# Board-Power.net
KiCad netlist of a schematic drawn in Altium Designer
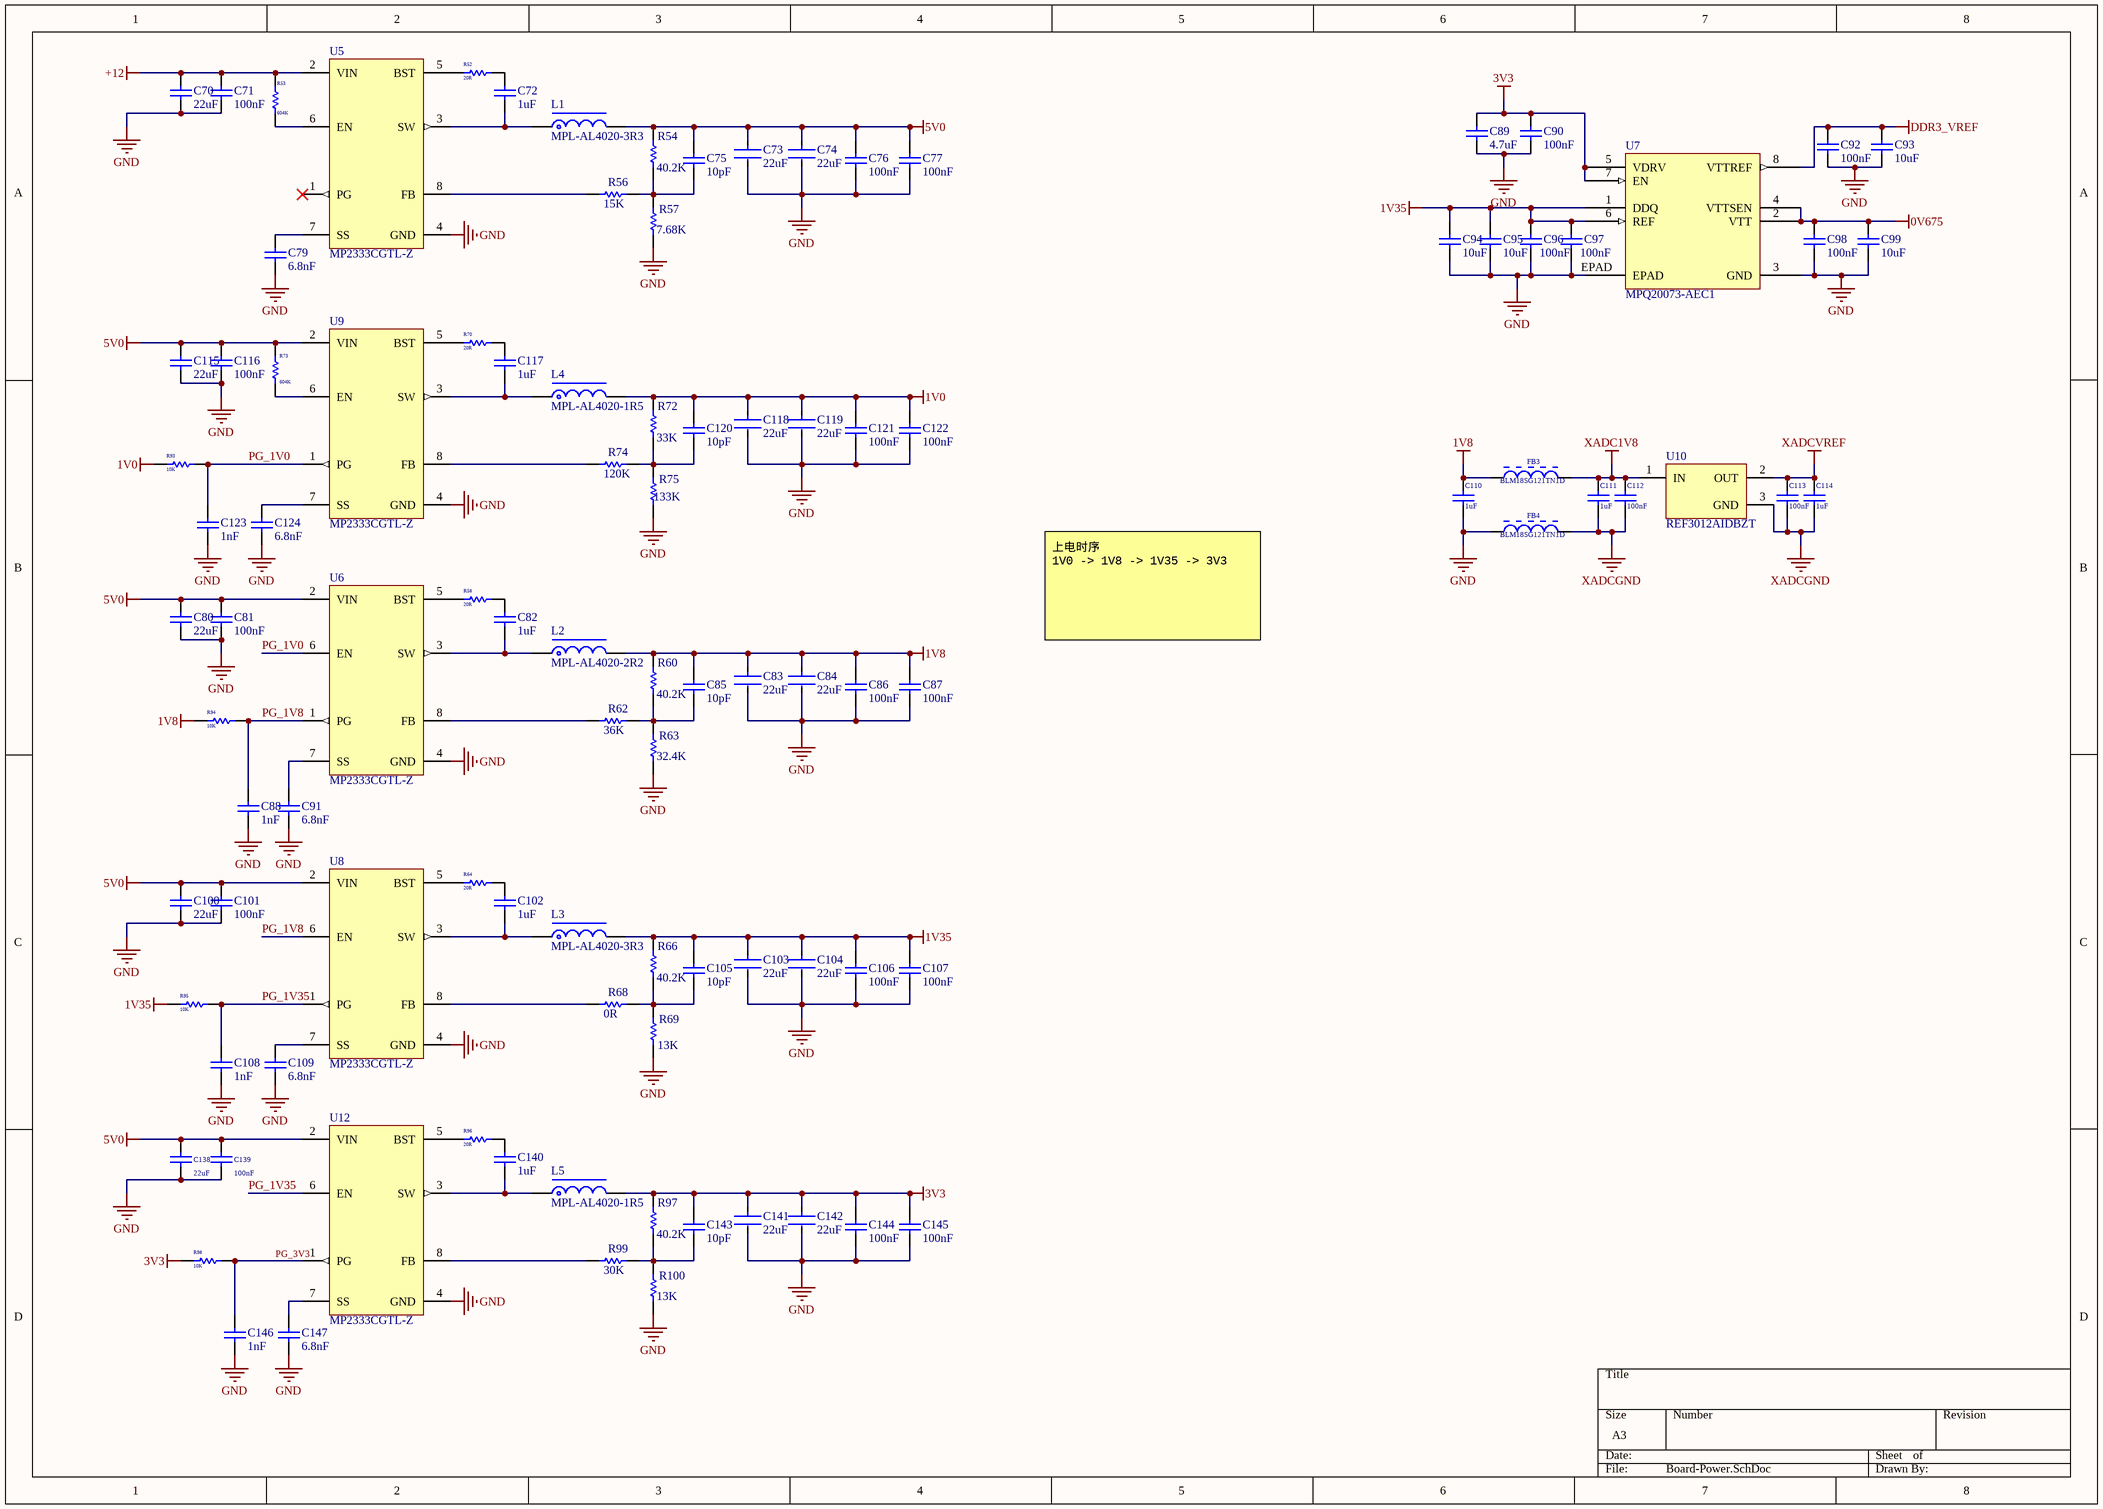
[diagram p0: Board-Power.SchDoc]

(export (version "E")
  (design (tool "Eeschema 10.0.6"))
  (components
    (comp (ref "C70")
      (value "22uF")
      (footprint "CAPC2013X145X45LL20T25")
      (description "GRM21BR61E226ME44L")
      (fields (field (name "MANUFACTURER") "Murata"))
      (libsource (lib "Altium Content Vault") (part "CAP"))
    )
    (comp (ref "C71")
      (value "100nF")
      (footprint "CAPC1005X55X25LL05T10")
      (fields (field (name "PART NUMBER") "GRM155R71H104KE14D") (field (name "MANUFACTURER") "Murata"))
      (libsource (lib "Altium Content Vault") (part "CAP"))
    )
    (comp (ref "C72")
      (value "1uF")
      (footprint "CAPC1005X55X25LL05T10")
      (fields (field (name "PART NUMBER") "GRM155R71H104KE14D") (field (name "MANUFACTURER") "Murata"))
      (libsource (lib "Altium Content Vault") (part "CAP"))
    )
    (comp (ref "C73")
      (value "22uF")
      (footprint "FP-GCM31C-0_2-e0_3_0_8-IPC_C")
      (description "GCM31CR71A226KE02K\r\nCap, Aec-Q200, 22Uf, 10V, Mlcc, 1206 Rohs Compliant: Yes")
      (libsource (lib "HainanU-RoboMaster-硬件组") (part "11868f565c42a9108669ba33697ecf6"))
    )
    (comp (ref "C74")
      (value "22uF")
      (footprint "FP-GCM31C-0_2-e0_3_0_8-IPC_C")
      (description "GCM31CR71A226KE02K\r\nCap, Aec-Q200, 22Uf, 10V, Mlcc, 1206 Rohs Compliant: Yes")
      (libsource (lib "HainanU-RoboMaster-硬件组") (part "11868f565c42a9108669ba33697ecf6"))
    )
    (comp (ref "C75")
      (value "10pF")
      (footprint "CAPC1005X55X25LL05T10")
      (fields (field (name "PART NUMBER") "GRM155R71H104KE14D") (field (name "MANUFACTURER") "Murata"))
      (libsource (lib "Altium Content Vault") (part "CAP"))
    )
    (comp (ref "C76")
      (value "100nF")
      (footprint "CAPC1005X55X25LL05T10")
      (fields (field (name "PART NUMBER") "GRM155R71H104KE14D") (field (name "MANUFACTURER") "Murata"))
      (libsource (lib "Altium Content Vault") (part "CAP"))
    )
    (comp (ref "C77")
      (value "100nF")
      (footprint "CAPC1005X55X25LL05T10")
      (fields (field (name "PART NUMBER") "GRM155R71H104KE14D") (field (name "MANUFACTURER") "Murata"))
      (libsource (lib "Altium Content Vault") (part "CAP"))
    )
    (comp (ref "C79")
      (value "6.8nF")
      (footprint "CAPC1005X55X25LL05T10")
      (fields (field (name "PART NUMBER") "GRM155R71H104KE14D") (field (name "MANUFACTURER") "Murata"))
      (libsource (lib "Altium Content Vault") (part "CAP"))
    )
    (comp (ref "C80")
      (value "22uF")
      (footprint "CAPC2013X145X45LL20T25")
      (description "GRM21BR61E226ME44L")
      (fields (field (name "MANUFACTURER") "Murata"))
      (libsource (lib "Altium Content Vault") (part "CAP"))
    )
    (comp (ref "C81")
      (value "100nF")
      (footprint "CAPC1005X55X25LL05T10")
      (fields (field (name "PART NUMBER") "GRM155R71H104KE14D") (field (name "MANUFACTURER") "Murata"))
      (libsource (lib "Altium Content Vault") (part "CAP"))
    )
    (comp (ref "C82")
      (value "1uF")
      (footprint "CAPC1005X55X25LL05T10")
      (fields (field (name "PART NUMBER") "GRM155R71H104KE14D") (field (name "MANUFACTURER") "Murata"))
      (libsource (lib "Altium Content Vault") (part "CAP"))
    )
    (comp (ref "C83")
      (value "22uF")
      (footprint "FP-GCM31C-0_2-e0_3_0_8-IPC_C")
      (description "GCM31CR71A226KE02K\r\nCap, Aec-Q200, 22Uf, 10V, Mlcc, 1206 Rohs Compliant: Yes")
      (libsource (lib "HainanU-RoboMaster-硬件组") (part "11868f565c42a9108669ba33697ecf6"))
    )
    (comp (ref "C84")
      (value "22uF")
      (footprint "FP-GCM31C-0_2-e0_3_0_8-IPC_C")
      (description "GCM31CR71A226KE02K\r\nCap, Aec-Q200, 22Uf, 10V, Mlcc, 1206 Rohs Compliant: Yes")
      (libsource (lib "HainanU-RoboMaster-硬件组") (part "11868f565c42a9108669ba33697ecf6"))
    )
    (comp (ref "C85")
      (value "10pF")
      (footprint "CAPC1005X55X25LL05T10")
      (fields (field (name "PART NUMBER") "GRM155R71H104KE14D") (field (name "MANUFACTURER") "Murata"))
      (libsource (lib "Altium Content Vault") (part "CAP"))
    )
    (comp (ref "C86")
      (value "100nF")
      (footprint "CAPC1005X55X25LL05T10")
      (fields (field (name "PART NUMBER") "GRM155R71H104KE14D") (field (name "MANUFACTURER") "Murata"))
      (libsource (lib "Altium Content Vault") (part "CAP"))
    )
    (comp (ref "C87")
      (value "100nF")
      (footprint "CAPC1005X55X25LL05T10")
      (fields (field (name "PART NUMBER") "GRM155R71H104KE14D") (field (name "MANUFACTURER") "Murata"))
      (libsource (lib "Altium Content Vault") (part "CAP"))
    )
    (comp (ref "C88")
      (value "1nF")
      (footprint "CAPC1005X55X25LL05T10")
      (fields (field (name "PART NUMBER") "GRM155R71H104KE14D") (field (name "MANUFACTURER") "Murata"))
      (libsource (lib "Altium Content Vault") (part "CAP"))
    )
    (comp (ref "C89")
      (value "4.7uF")
      (footprint "CAPC1005X55X25LL05T10")
      (fields (field (name "PART NUMBER") "GRM155R71H104KE14D") (field (name "MANUFACTURER") "Murata"))
      (libsource (lib "Altium Content Vault") (part "CAP"))
    )
    (comp (ref "C90")
      (value "100nF")
      (footprint "CAPC1005X55X25LL05T10")
      (fields (field (name "PART NUMBER") "GRM155R71H104KE14D") (field (name "MANUFACTURER") "Murata"))
      (libsource (lib "Altium Content Vault") (part "CAP"))
    )
    (comp (ref "C91")
      (value "6.8nF")
      (footprint "CAPC1005X55X25LL05T10")
      (fields (field (name "PART NUMBER") "GRM155R71H104KE14D") (field (name "MANUFACTURER") "Murata"))
      (libsource (lib "Altium Content Vault") (part "CAP"))
    )
    (comp (ref "C92")
      (value "100nF")
      (footprint "CAPC1005X55X25LL05T10")
      (fields (field (name "PART NUMBER") "GRM155R71H104KE14D") (field (name "MANUFACTURER") "Murata"))
      (libsource (lib "Altium Content Vault") (part "CAP"))
    )
    (comp (ref "C93")
      (value "10uF")
      (footprint "MURA-1206_H_1.8_L")
      (description "GRM31CR61H106KA12L\r\nCAP, Ceramic, 10 uF, 10%, 50 V, 1206, RoHS, Tape and Reel")
      (fields (field (name "TOLERANCE") "10%") (field (name "MANUFACTURER") "Murata"))
      (libsource (lib "Altium Content Vault") (part "CAP-NP-2"))
    )
    (comp (ref "C94")
      (value "10uF")
      (footprint "MURA-1206_H_1.8_L")
      (description "GRM31CR61H106KA12L\r\nCAP, Ceramic, 10 uF, 10%, 50 V, 1206, RoHS, Tape and Reel")
      (fields (field (name "TOLERANCE") "10%") (field (name "MANUFACTURER") "Murata"))
      (libsource (lib "Altium Content Vault") (part "CAP-NP-2"))
    )
    (comp (ref "C95")
      (value "10uF")
      (footprint "MURA-1206_H_1.8_L")
      (description "GRM31CR61H106KA12L\r\nCAP, Ceramic, 10 uF, 10%, 50 V, 1206, RoHS, Tape and Reel")
      (fields (field (name "TOLERANCE") "10%") (field (name "MANUFACTURER") "Murata"))
      (libsource (lib "Altium Content Vault") (part "CAP-NP-2"))
    )
    (comp (ref "C96")
      (value "100nF")
      (footprint "CAPC1005X55X25LL05T10")
      (fields (field (name "PART NUMBER") "GRM155R71H104KE14D") (field (name "MANUFACTURER") "Murata"))
      (libsource (lib "Altium Content Vault") (part "CAP"))
    )
    (comp (ref "C97")
      (value "100nF")
      (footprint "CAPC1005X55X25LL05T10")
      (fields (field (name "PART NUMBER") "GRM155R71H104KE14D") (field (name "MANUFACTURER") "Murata"))
      (libsource (lib "Altium Content Vault") (part "CAP"))
    )
    (comp (ref "C98")
      (value "100nF")
      (footprint "CAPC1005X55X25LL05T10")
      (fields (field (name "PART NUMBER") "GRM155R71H104KE14D") (field (name "MANUFACTURER") "Murata"))
      (libsource (lib "Altium Content Vault") (part "CAP"))
    )
    (comp (ref "C99")
      (value "10uF")
      (footprint "MURA-1206_H_1.8_L")
      (description "GRM31CR61H106KA12L\r\nCAP, Ceramic, 10 uF, 10%, 50 V, 1206, RoHS, Tape and Reel")
      (fields (field (name "TOLERANCE") "10%") (field (name "MANUFACTURER") "Murata"))
      (libsource (lib "Altium Content Vault") (part "CAP-NP-2"))
    )
    (comp (ref "C100")
      (value "22uF")
      (footprint "CAPC2013X145X45LL20T25")
      (description "GRM21BR61E226ME44L")
      (fields (field (name "MANUFACTURER") "Murata"))
      (libsource (lib "Altium Content Vault") (part "CAP"))
    )
    (comp (ref "C101")
      (value "100nF")
      (footprint "CAPC1005X55X25LL05T10")
      (fields (field (name "PART NUMBER") "GRM155R71H104KE14D") (field (name "MANUFACTURER") "Murata"))
      (libsource (lib "Altium Content Vault") (part "CAP"))
    )
    (comp (ref "C102")
      (value "1uF")
      (footprint "CAPC1005X55X25LL05T10")
      (fields (field (name "PART NUMBER") "GRM155R71H104KE14D") (field (name "MANUFACTURER") "Murata"))
      (libsource (lib "Altium Content Vault") (part "CAP"))
    )
    (comp (ref "C103")
      (value "22uF")
      (footprint "FP-GCM31C-0_2-e0_3_0_8-IPC_C")
      (description "GCM31CR71A226KE02K\r\nCap, Aec-Q200, 22Uf, 10V, Mlcc, 1206 Rohs Compliant: Yes")
      (libsource (lib "HainanU-RoboMaster-硬件组") (part "11868f565c42a9108669ba33697ecf6"))
    )
    (comp (ref "C104")
      (value "22uF")
      (footprint "FP-GCM31C-0_2-e0_3_0_8-IPC_C")
      (description "GCM31CR71A226KE02K\r\nCap, Aec-Q200, 22Uf, 10V, Mlcc, 1206 Rohs Compliant: Yes")
      (libsource (lib "HainanU-RoboMaster-硬件组") (part "11868f565c42a9108669ba33697ecf6"))
    )
    (comp (ref "C105")
      (value "10pF")
      (footprint "CAPC1005X55X25LL05T10")
      (fields (field (name "PART NUMBER") "GRM155R71H104KE14D") (field (name "MANUFACTURER") "Murata"))
      (libsource (lib "Altium Content Vault") (part "CAP"))
    )
    (comp (ref "C106")
      (value "100nF")
      (footprint "CAPC1005X55X25LL05T10")
      (fields (field (name "PART NUMBER") "GRM155R71H104KE14D") (field (name "MANUFACTURER") "Murata"))
      (libsource (lib "Altium Content Vault") (part "CAP"))
    )
    (comp (ref "C107")
      (value "100nF")
      (footprint "CAPC1005X55X25LL05T10")
      (fields (field (name "PART NUMBER") "GRM155R71H104KE14D") (field (name "MANUFACTURER") "Murata"))
      (libsource (lib "Altium Content Vault") (part "CAP"))
    )
    (comp (ref "C108")
      (value "1nF")
      (footprint "CAPC1005X55X25LL05T10")
      (fields (field (name "PART NUMBER") "GRM155R71H104KE14D") (field (name "MANUFACTURER") "Murata"))
      (libsource (lib "Altium Content Vault") (part "CAP"))
    )
    (comp (ref "C109")
      (value "6.8nF")
      (footprint "CAPC1005X55X25LL05T10")
      (fields (field (name "PART NUMBER") "GRM155R71H104KE14D") (field (name "MANUFACTURER") "Murata"))
      (libsource (lib "Altium Content Vault") (part "CAP"))
    )
    (comp (ref "C110")
      (value "1uF")
      (footprint "CAPC1005X55X25LL05T10")
      (fields (field (name "PART NUMBER") "GRM155R71H104KE14D") (field (name "MANUFACTURER") "Murata"))
      (libsource (lib "Altium Content Vault") (part "CAP"))
    )
    (comp (ref "C111")
      (value "1uF")
      (footprint "CAPC1005X55X25LL05T10")
      (fields (field (name "PART NUMBER") "GRM155R71H104KE14D") (field (name "MANUFACTURER") "Murata"))
      (libsource (lib "Altium Content Vault") (part "CAP"))
    )
    (comp (ref "C112")
      (value "100nF")
      (footprint "CAPC1005X55X25LL05T10")
      (fields (field (name "PART NUMBER") "GRM155R71H104KE14D") (field (name "MANUFACTURER") "Murata"))
      (libsource (lib "Altium Content Vault") (part "CAP"))
    )
    (comp (ref "C113")
      (value "100nF")
      (footprint "CAPC1005X55X25LL05T10")
      (fields (field (name "PART NUMBER") "GRM155R71H104KE14D") (field (name "MANUFACTURER") "Murata"))
      (libsource (lib "Altium Content Vault") (part "CAP"))
    )
    (comp (ref "C114")
      (value "1uF")
      (footprint "CAPC1005X55X25LL05T10")
      (fields (field (name "PART NUMBER") "GRM155R71H104KE14D") (field (name "MANUFACTURER") "Murata"))
      (libsource (lib "Altium Content Vault") (part "CAP"))
    )
    (comp (ref "C115")
      (value "22uF")
      (footprint "CAPC2013X145X45LL20T25")
      (description "GRM21BR61E226ME44L")
      (fields (field (name "MANUFACTURER") "Murata"))
      (libsource (lib "Altium Content Vault") (part "CAP"))
    )
    (comp (ref "C116")
      (value "100nF")
      (footprint "CAPC1005X55X25LL05T10")
      (fields (field (name "PART NUMBER") "GRM155R71H104KE14D") (field (name "MANUFACTURER") "Murata"))
      (libsource (lib "Altium Content Vault") (part "CAP"))
    )
    (comp (ref "C117")
      (value "1uF")
      (footprint "CAPC1005X55X25LL05T10")
      (fields (field (name "PART NUMBER") "GRM155R71H104KE14D") (field (name "MANUFACTURER") "Murata"))
      (libsource (lib "Altium Content Vault") (part "CAP"))
    )
    (comp (ref "C118")
      (value "22uF")
      (footprint "FP-GCM31C-0_2-e0_3_0_8-IPC_C")
      (description "GCM31CR71A226KE02K\r\nCap, Aec-Q200, 22Uf, 10V, Mlcc, 1206 Rohs Compliant: Yes")
      (libsource (lib "HainanU-RoboMaster-硬件组") (part "11868f565c42a9108669ba33697ecf6"))
    )
    (comp (ref "C119")
      (value "22uF")
      (footprint "FP-GCM31C-0_2-e0_3_0_8-IPC_C")
      (description "GCM31CR71A226KE02K\r\nCap, Aec-Q200, 22Uf, 10V, Mlcc, 1206 Rohs Compliant: Yes")
      (libsource (lib "HainanU-RoboMaster-硬件组") (part "11868f565c42a9108669ba33697ecf6"))
    )
    (comp (ref "C120")
      (value "10pF")
      (footprint "CAPC1005X55X25LL05T10")
      (fields (field (name "PART NUMBER") "GRM155R71H104KE14D") (field (name "MANUFACTURER") "Murata"))
      (libsource (lib "Altium Content Vault") (part "CAP"))
    )
    (comp (ref "C121")
      (value "100nF")
      (footprint "CAPC1005X55X25LL05T10")
      (fields (field (name "PART NUMBER") "GRM155R71H104KE14D") (field (name "MANUFACTURER") "Murata"))
      (libsource (lib "Altium Content Vault") (part "CAP"))
    )
    (comp (ref "C122")
      (value "100nF")
      (footprint "CAPC1005X55X25LL05T10")
      (fields (field (name "PART NUMBER") "GRM155R71H104KE14D") (field (name "MANUFACTURER") "Murata"))
      (libsource (lib "Altium Content Vault") (part "CAP"))
    )
    (comp (ref "C123")
      (value "1nF")
      (footprint "CAPC1005X55X25LL05T10")
      (fields (field (name "PART NUMBER") "GRM155R71H104KE14D") (field (name "MANUFACTURER") "Murata"))
      (libsource (lib "Altium Content Vault") (part "CAP"))
    )
    (comp (ref "C124")
      (value "6.8nF")
      (footprint "CAPC1005X55X25LL05T10")
      (fields (field (name "PART NUMBER") "GRM155R71H104KE14D") (field (name "MANUFACTURER") "Murata"))
      (libsource (lib "Altium Content Vault") (part "CAP"))
    )
    (comp (ref "C138")
      (value "22uF")
      (footprint "CAPC2013X145X45LL20T25")
      (description "GRM21BR61E226ME44L")
      (fields (field (name "MANUFACTURER") "Murata"))
      (libsource (lib "Altium Content Vault") (part "CAP"))
    )
    (comp (ref "C139")
      (value "100nF")
      (footprint "CAPC1005X55X25LL05T10")
      (fields (field (name "PART NUMBER") "GRM155R71H104KE14D") (field (name "MANUFACTURER") "Murata"))
      (libsource (lib "Altium Content Vault") (part "CAP"))
    )
    (comp (ref "C140")
      (value "1uF")
      (footprint "CAPC1005X55X25LL05T10")
      (fields (field (name "PART NUMBER") "GRM155R71H104KE14D") (field (name "MANUFACTURER") "Murata"))
      (libsource (lib "Altium Content Vault") (part "CAP"))
    )
    (comp (ref "C141")
      (value "22uF")
      (footprint "FP-GCM31C-0_2-e0_3_0_8-IPC_C")
      (description "GCM31CR71A226KE02K\r\nCap, Aec-Q200, 22Uf, 10V, Mlcc, 1206 Rohs Compliant: Yes")
      (libsource (lib "HainanU-RoboMaster-硬件组") (part "11868f565c42a9108669ba33697ecf6"))
    )
    (comp (ref "C142")
      (value "22uF")
      (footprint "FP-GCM31C-0_2-e0_3_0_8-IPC_C")
      (description "GCM31CR71A226KE02K\r\nCap, Aec-Q200, 22Uf, 10V, Mlcc, 1206 Rohs Compliant: Yes")
      (libsource (lib "HainanU-RoboMaster-硬件组") (part "11868f565c42a9108669ba33697ecf6"))
    )
    (comp (ref "C143")
      (value "10pF")
      (footprint "CAPC1005X55X25LL05T10")
      (fields (field (name "PART NUMBER") "GRM155R71H104KE14D") (field (name "MANUFACTURER") "Murata"))
      (libsource (lib "Altium Content Vault") (part "CAP"))
    )
    (comp (ref "C144")
      (value "100nF")
      (footprint "CAPC1005X55X25LL05T10")
      (fields (field (name "PART NUMBER") "GRM155R71H104KE14D") (field (name "MANUFACTURER") "Murata"))
      (libsource (lib "Altium Content Vault") (part "CAP"))
    )
    (comp (ref "C145")
      (value "100nF")
      (footprint "CAPC1005X55X25LL05T10")
      (fields (field (name "PART NUMBER") "GRM155R71H104KE14D") (field (name "MANUFACTURER") "Murata"))
      (libsource (lib "Altium Content Vault") (part "CAP"))
    )
    (comp (ref "C146")
      (value "1nF")
      (footprint "CAPC1005X55X25LL05T10")
      (fields (field (name "PART NUMBER") "GRM155R71H104KE14D") (field (name "MANUFACTURER") "Murata"))
      (libsource (lib "Altium Content Vault") (part "CAP"))
    )
    (comp (ref "C147")
      (value "6.8nF")
      (footprint "CAPC1005X55X25LL05T10")
      (fields (field (name "PART NUMBER") "GRM155R71H104KE14D") (field (name "MANUFACTURER") "Murata"))
      (libsource (lib "Altium Content Vault") (part "CAP"))
    )
    (comp (ref "FB3")
      (value "BLM18SG121TN1D")
      (footprint "MURA-BLM18SG-B40-CHIP-2_V6")
      (fields (field (name "MANUFACTURER") "Murata"))
      (libsource (lib "Altium Content Vault") (part "MURA-FB-2"))
    )
    (comp (ref "FB4")
      (value "BLM18SG121TN1D")
      (footprint "MURA-BLM18SG-B40-CHIP-2_V6")
      (fields (field (name "MANUFACTURER") "Murata"))
      (libsource (lib "Altium Content Vault") (part "MURA-FB-2"))
    )
    (comp (ref "L1")
      (value "MPL-AL4020-3R3")
      (footprint "MPL-AL4020")
      (description "一体成型电感")
      (libsource (lib "0.1 - 电阻-电容-电感-保险丝-晶振-晶体-磁珠-电位器-法拉电容-馈通电容") (part "L-Molding Choke"))
    )
    (comp (ref "L2")
      (value "MPL-AL4020-2R2")
      (footprint "MPL-AL4020")
      (description "一体成型电感")
      (libsource (lib "0.1 - 电阻-电容-电感-保险丝-晶振-晶体-磁珠-电位器-法拉电容-馈通电容") (part "L-Molding Choke"))
    )
    (comp (ref "L3")
      (value "MPL-AL4020-3R3")
      (footprint "MPL-AL4020")
      (description "一体成型电感")
      (libsource (lib "0.1 - 电阻-电容-电感-保险丝-晶振-晶体-磁珠-电位器-法拉电容-馈通电容") (part "L-Molding Choke"))
    )
    (comp (ref "L4")
      (value "MPL-AL4020-1R5")
      (footprint "MPL-AL4020")
      (description "一体成型电感")
      (libsource (lib "0.1 - 电阻-电容-电感-保险丝-晶振-晶体-磁珠-电位器-法拉电容-馈通电容") (part "L-Molding Choke"))
    )
    (comp (ref "L5")
      (value "MPL-AL4020-1R5")
      (footprint "MPL-AL4020")
      (description "一体成型电感")
      (libsource (lib "0.1 - 电阻-电容-电感-保险丝-晶振-晶体-磁珠-电位器-法拉电容-馈通电容") (part "L-Molding Choke"))
    )
    (comp (ref "R52")
      (value "20R")
      (footprint "RESC1005X40X25LL05T05")
      (fields (field (name "MANUFACTURER") "Panasonic") (field (name "PART NUMBER") "ERJ-2RKF40R2X"))
      (libsource (lib "Altium Content Vault") (part "RES"))
    )
    (comp (ref "R53")
      (value "604K")
      (footprint "RESC1005X40X25LL05T05")
      (fields (field (name "MANUFACTURER") "Panasonic") (field (name "PART NUMBER") "ERJ-2RKF40R2X"))
      (libsource (lib "Altium Content Vault") (part "RES"))
    )
    (comp (ref "R54")
      (value "40.2K")
      (footprint "RESC1005X40X25LL05T05")
      (fields (field (name "MANUFACTURER") "Panasonic") (field (name "PART NUMBER") "ERJ-2RKF40R2X"))
      (libsource (lib "Altium Content Vault") (part "RES"))
    )
    (comp (ref "R56")
      (value "15K")
      (footprint "RESC1005X40X25LL05T05")
      (fields (field (name "MANUFACTURER") "Panasonic") (field (name "PART NUMBER") "ERJ-2RKF40R2X"))
      (libsource (lib "Altium Content Vault") (part "RES"))
    )
    (comp (ref "R57")
      (value "7.68K")
      (footprint "RESC1005X40X25LL05T05")
      (fields (field (name "MANUFACTURER") "Panasonic") (field (name "PART NUMBER") "ERJ-2RKF40R2X"))
      (libsource (lib "Altium Content Vault") (part "RES"))
    )
    (comp (ref "R58")
      (value "20R")
      (footprint "RESC1005X40X25LL05T05")
      (fields (field (name "MANUFACTURER") "Panasonic") (field (name "PART NUMBER") "ERJ-2RKF40R2X"))
      (libsource (lib "Altium Content Vault") (part "RES"))
    )
    (comp (ref "R60")
      (value "40.2K")
      (footprint "RESC1005X40X25LL05T05")
      (fields (field (name "MANUFACTURER") "Panasonic") (field (name "PART NUMBER") "ERJ-2RKF40R2X"))
      (libsource (lib "Altium Content Vault") (part "RES"))
    )
    (comp (ref "R62")
      (value "36K")
      (footprint "RESC1005X40X25LL05T05")
      (fields (field (name "MANUFACTURER") "Panasonic") (field (name "PART NUMBER") "ERJ-2RKF40R2X"))
      (libsource (lib "Altium Content Vault") (part "RES"))
    )
    (comp (ref "R63")
      (value "32.4K")
      (footprint "RESC1005X40X25LL05T05")
      (fields (field (name "MANUFACTURER") "Panasonic") (field (name "PART NUMBER") "ERJ-2RKF40R2X"))
      (libsource (lib "Altium Content Vault") (part "RES"))
    )
    (comp (ref "R64")
      (value "20R")
      (footprint "RESC1005X40X25LL05T05")
      (fields (field (name "MANUFACTURER") "Panasonic") (field (name "PART NUMBER") "ERJ-2RKF40R2X"))
      (libsource (lib "Altium Content Vault") (part "RES"))
    )
    (comp (ref "R66")
      (value "40.2K")
      (footprint "RESC1005X40X25LL05T05")
      (fields (field (name "MANUFACTURER") "Panasonic") (field (name "PART NUMBER") "ERJ-2RKF40R2X"))
      (libsource (lib "Altium Content Vault") (part "RES"))
    )
    (comp (ref "R68")
      (value "0R")
      (footprint "RESC1005X40X25LL05T05")
      (fields (field (name "MANUFACTURER") "Panasonic") (field (name "PART NUMBER") "ERJ-2RKF40R2X"))
      (libsource (lib "Altium Content Vault") (part "RES"))
    )
    (comp (ref "R69")
      (value "13K")
      (footprint "RESC1005X40X25LL05T05")
      (fields (field (name "MANUFACTURER") "Panasonic") (field (name "PART NUMBER") "ERJ-2RKF40R2X"))
      (libsource (lib "Altium Content Vault") (part "RES"))
    )
    (comp (ref "R70")
      (value "20R")
      (footprint "RESC1005X40X25LL05T05")
      (fields (field (name "MANUFACTURER") "Panasonic") (field (name "PART NUMBER") "ERJ-2RKF40R2X"))
      (libsource (lib "Altium Content Vault") (part "RES"))
    )
    (comp (ref "R72")
      (value "33K")
      (footprint "RESC1005X40X25LL05T05")
      (fields (field (name "MANUFACTURER") "Panasonic") (field (name "PART NUMBER") "ERJ-2RKF40R2X"))
      (libsource (lib "Altium Content Vault") (part "RES"))
    )
    (comp (ref "R73")
      (value "604K")
      (footprint "RESC1005X40X25LL05T05")
      (fields (field (name "MANUFACTURER") "Panasonic") (field (name "PART NUMBER") "ERJ-2RKF40R2X"))
      (libsource (lib "Altium Content Vault") (part "RES"))
    )
    (comp (ref "R74")
      (value "120K")
      (footprint "RESC1005X40X25LL05T05")
      (fields (field (name "MANUFACTURER") "Panasonic") (field (name "PART NUMBER") "ERJ-2RKF40R2X"))
      (libsource (lib "Altium Content Vault") (part "RES"))
    )
    (comp (ref "R75")
      (value "133K")
      (footprint "RESC1005X40X25LL05T05")
      (fields (field (name "MANUFACTURER") "Panasonic") (field (name "PART NUMBER") "ERJ-2RKF40R2X"))
      (libsource (lib "Altium Content Vault") (part "RES"))
    )
    (comp (ref "R93")
      (value "10K")
      (footprint "RESC1005X40X25LL05T05")
      (fields (field (name "MANUFACTURER") "Panasonic") (field (name "PART NUMBER") "ERJ-2RKF40R2X"))
      (libsource (lib "Altium Content Vault") (part "RES"))
    )
    (comp (ref "R94")
      (value "10K")
      (footprint "RESC1005X40X25LL05T05")
      (fields (field (name "MANUFACTURER") "Panasonic") (field (name "PART NUMBER") "ERJ-2RKF40R2X"))
      (libsource (lib "Altium Content Vault") (part "RES"))
    )
    (comp (ref "R95")
      (value "10K")
      (footprint "RESC1005X40X25LL05T05")
      (fields (field (name "MANUFACTURER") "Panasonic") (field (name "PART NUMBER") "ERJ-2RKF40R2X"))
      (libsource (lib "Altium Content Vault") (part "RES"))
    )
    (comp (ref "R96")
      (value "20R")
      (footprint "RESC1005X40X25LL05T05")
      (fields (field (name "MANUFACTURER") "Panasonic") (field (name "PART NUMBER") "ERJ-2RKF40R2X"))
      (libsource (lib "Altium Content Vault") (part "RES"))
    )
    (comp (ref "R97")
      (value "40.2K")
      (footprint "RESC1005X40X25LL05T05")
      (fields (field (name "MANUFACTURER") "Panasonic") (field (name "PART NUMBER") "ERJ-2RKF40R2X"))
      (libsource (lib "Altium Content Vault") (part "RES"))
    )
    (comp (ref "R98")
      (value "10K")
      (footprint "RESC1005X40X25LL05T05")
      (fields (field (name "MANUFACTURER") "Panasonic") (field (name "PART NUMBER") "ERJ-2RKF40R2X"))
      (libsource (lib "Altium Content Vault") (part "RES"))
    )
    (comp (ref "R99")
      (value "30K")
      (footprint "RESC1005X40X25LL05T05")
      (fields (field (name "MANUFACTURER") "Panasonic") (field (name "PART NUMBER") "ERJ-2RKF40R2X"))
      (libsource (lib "Altium Content Vault") (part "RES"))
    )
    (comp (ref "R100")
      (value "13K")
      (footprint "RESC1005X40X25LL05T05")
      (fields (field (name "MANUFACTURER") "Panasonic") (field (name "PART NUMBER") "ERJ-2RKF40R2X"))
      (libsource (lib "Altium Content Vault") (part "RES"))
    )
    (comp (ref "U5")
      (value "MP2333CGTL-Z")
      (footprint "SOT583_MP2333C_MNP")
      (description "Switching Voltage Regulators 3A, 18V, 650kHz, Force CCM, Synchronous Step-Down C")
      (libsource (lib "HainanU-RoboMaster-硬件组") (part "MP2333CGTL-Z"))
    )
    (comp (ref "U6")
      (value "MP2333CGTL-Z")
      (footprint "SOT583_MP2333C_MNP")
      (description "Switching Voltage Regulators 3A, 18V, 650kHz, Force CCM, Synchronous Step-Down C")
      (libsource (lib "HainanU-RoboMaster-硬件组") (part "MP2333CGTL-Z"))
    )
    (comp (ref "U7")
      (value "MPQ20073-AEC1")
      (footprint "MSOP-8-EP_MNP-L")
      (description "2A 1.3V–6.0V DDR Memory Termination Regulator AEC-Q100 Qualified")
      (libsource (lib "HainanU-RoboMaster-硬件组") (part "MPQ20073DH-AEC1-LF-P"))
    )
    (comp (ref "U8")
      (value "MP2333CGTL-Z")
      (footprint "SOT583_MP2333C_MNP")
      (description "Switching Voltage Regulators 3A, 18V, 650kHz, Force CCM, Synchronous Step-Down C")
      (libsource (lib "HainanU-RoboMaster-硬件组") (part "MP2333CGTL-Z"))
    )
    (comp (ref "U9")
      (value "MP2333CGTL-Z")
      (footprint "SOT583_MP2333C_MNP")
      (description "Switching Voltage Regulators 3A, 18V, 650kHz, Force CCM, Synchronous Step-Down C")
      (libsource (lib "HainanU-RoboMaster-硬件组") (part "MP2333CGTL-Z"))
    )
    (comp (ref "U10")
      (value "REF3012AIDBZT")
      (footprint "DBZ0003A_L")
      (fields (field (name "MANUFACTURER") "Texas Instruments"))
      (libsource (lib "Altium Content Vault") (part "TI-REF3012DBZ3"))
    )
    (comp (ref "U12")
      (value "MP2333CGTL-Z")
      (footprint "SOT583_MP2333C_MNP")
      (description "Switching Voltage Regulators 3A, 18V, 650kHz, Force CCM, Synchronous Step-Down C")
      (libsource (lib "HainanU-RoboMaster-硬件组") (part "MP2333CGTL-Z"))
    )
  )
  (nets
    (net (code "1") (name "+12") (class "Default")
      (node (ref "C70") (pin "2") (pinfunction "2_2") (pintype "passive"))
      (node (ref "C71") (pin "2") (pinfunction "2_2") (pintype "passive"))
      (node (ref "R53") (pin "2") (pinfunction "2_2") (pintype "passive"))
      (node (ref "U5") (pin "2") (pinfunction "VIN_2") (pintype "power_in"))
    )
    (net (code "2") (name "/PG_1V0") (class "Default")
      (node (ref "C123") (pin "1") (pinfunction "1_1") (pintype "passive"))
      (node (ref "R93") (pin "1") (pinfunction "1_1") (pintype "passive"))
      (node (ref "U6") (pin "6") (pinfunction "EN_6") (pintype "passive"))
      (node (ref "U9") (pin "1") (pinfunction "PG_1") (pintype "output"))
    )
    (net (code "3") (name "/PG_1V8") (class "Default")
      (node (ref "C88") (pin "1") (pinfunction "1_1") (pintype "passive"))
      (node (ref "R94") (pin "1") (pinfunction "1_1") (pintype "passive"))
      (node (ref "U6") (pin "1") (pinfunction "PG_1") (pintype "output"))
      (node (ref "U8") (pin "6") (pinfunction "EN_6") (pintype "passive"))
    )
    (net (code "4") (name "/PG_1V35") (class "Default")
      (node (ref "C108") (pin "1") (pinfunction "1_1") (pintype "passive"))
      (node (ref "R95") (pin "1") (pinfunction "1_1") (pintype "passive"))
      (node (ref "U12") (pin "6") (pinfunction "EN_6") (pintype "passive"))
      (node (ref "U8") (pin "1") (pinfunction "PG_1") (pintype "output"))
    )
    (net (code "5") (name "/PG_3V3") (class "Default")
      (node (ref "C146") (pin "1") (pinfunction "1_1") (pintype "passive"))
      (node (ref "R98") (pin "1") (pinfunction "1_1") (pintype "passive"))
      (node (ref "U12") (pin "1") (pinfunction "PG_1") (pintype "output"))
    )
    (net (code "6") (name "0V675") (class "Default")
      (node (ref "C98") (pin "2") (pinfunction "2_2") (pintype "passive"))
      (node (ref "C99") (pin "2") (pinfunction "2_2") (pintype "passive"))
      (node (ref "U7") (pin "2") (pinfunction "VTT_2") (pintype "power_in"))
      (node (ref "U7") (pin "4") (pinfunction "VTTSEN_4") (pintype "passive"))
    )
    (net (code "7") (name "1V0") (class "Default")
      (node (ref "C118") (pin "1") (pinfunction "1_1") (pintype "passive"))
      (node (ref "C119") (pin "1") (pinfunction "1_1") (pintype "passive"))
      (node (ref "C120") (pin "2") (pinfunction "2_2") (pintype "passive"))
      (node (ref "C121") (pin "2") (pinfunction "2_2") (pintype "passive"))
      (node (ref "C122") (pin "2") (pinfunction "2_2") (pintype "passive"))
      (node (ref "L4") (pin "2") (pinfunction "2_2") (pintype "passive"))
      (node (ref "R72") (pin "1") (pinfunction "1_1") (pintype "passive"))
      (node (ref "R93") (pin "2") (pinfunction "2_2") (pintype "passive"))
    )
    (net (code "8") (name "1V8") (class "Default")
      (node (ref "C110") (pin "2") (pinfunction "2_2") (pintype "passive"))
      (node (ref "C83") (pin "1") (pinfunction "1_1") (pintype "passive"))
      (node (ref "C84") (pin "1") (pinfunction "1_1") (pintype "passive"))
      (node (ref "C85") (pin "2") (pinfunction "2_2") (pintype "passive"))
      (node (ref "C86") (pin "2") (pinfunction "2_2") (pintype "passive"))
      (node (ref "C87") (pin "2") (pinfunction "2_2") (pintype "passive"))
      (node (ref "FB3") (pin "1") (pinfunction "1_1") (pintype "passive"))
      (node (ref "L2") (pin "2") (pinfunction "2_2") (pintype "passive"))
      (node (ref "R60") (pin "1") (pinfunction "1_1") (pintype "passive"))
      (node (ref "R94") (pin "2") (pinfunction "2_2") (pintype "passive"))
    )
    (net (code "9") (name "1V35") (class "Default")
      (node (ref "C103") (pin "1") (pinfunction "1_1") (pintype "passive"))
      (node (ref "C104") (pin "1") (pinfunction "1_1") (pintype "passive"))
      (node (ref "C105") (pin "2") (pinfunction "2_2") (pintype "passive"))
      (node (ref "C106") (pin "2") (pinfunction "2_2") (pintype "passive"))
      (node (ref "C107") (pin "2") (pinfunction "2_2") (pintype "passive"))
      (node (ref "C94") (pin "2") (pinfunction "2_2") (pintype "passive"))
      (node (ref "C95") (pin "2") (pinfunction "2_2") (pintype "passive"))
      (node (ref "C96") (pin "2") (pinfunction "2_2") (pintype "passive"))
      (node (ref "C97") (pin "2") (pinfunction "2_2") (pintype "passive"))
      (node (ref "L3") (pin "2") (pinfunction "2_2") (pintype "passive"))
      (node (ref "R66") (pin "1") (pinfunction "1_1") (pintype "passive"))
      (node (ref "R95") (pin "2") (pinfunction "2_2") (pintype "passive"))
      (node (ref "U7") (pin "1") (pinfunction "DDQ_1") (pintype "power_in"))
      (node (ref "U7") (pin "6") (pinfunction "REF_6") (pintype "input"))
    )
    (net (code "10") (name "3V3") (class "Default")
      (node (ref "C141") (pin "1") (pinfunction "1_1") (pintype "passive"))
      (node (ref "C142") (pin "1") (pinfunction "1_1") (pintype "passive"))
      (node (ref "C143") (pin "2") (pinfunction "2_2") (pintype "passive"))
      (node (ref "C144") (pin "2") (pinfunction "2_2") (pintype "passive"))
      (node (ref "C145") (pin "2") (pinfunction "2_2") (pintype "passive"))
      (node (ref "C89") (pin "2") (pinfunction "2_2") (pintype "passive"))
      (node (ref "C90") (pin "2") (pinfunction "2_2") (pintype "passive"))
      (node (ref "L5") (pin "2") (pinfunction "2_2") (pintype "passive"))
      (node (ref "R97") (pin "1") (pinfunction "1_1") (pintype "passive"))
      (node (ref "R98") (pin "2") (pinfunction "2_2") (pintype "passive"))
      (node (ref "U7") (pin "5") (pinfunction "VDRV_5") (pintype "passive"))
      (node (ref "U7") (pin "7") (pinfunction "EN_7") (pintype "input"))
    )
    (net (code "11") (name "5V0") (class "Default")
      (node (ref "C100") (pin "2") (pinfunction "2_2") (pintype "passive"))
      (node (ref "C101") (pin "2") (pinfunction "2_2") (pintype "passive"))
      (node (ref "C115") (pin "2") (pinfunction "2_2") (pintype "passive"))
      (node (ref "C116") (pin "2") (pinfunction "2_2") (pintype "passive"))
      (node (ref "C138") (pin "2") (pinfunction "2_2") (pintype "passive"))
      (node (ref "C139") (pin "2") (pinfunction "2_2") (pintype "passive"))
      (node (ref "C73") (pin "1") (pinfunction "1_1") (pintype "passive"))
      (node (ref "C74") (pin "1") (pinfunction "1_1") (pintype "passive"))
      (node (ref "C75") (pin "2") (pinfunction "2_2") (pintype "passive"))
      (node (ref "C76") (pin "2") (pinfunction "2_2") (pintype "passive"))
      (node (ref "C77") (pin "2") (pinfunction "2_2") (pintype "passive"))
      (node (ref "C80") (pin "2") (pinfunction "2_2") (pintype "passive"))
      (node (ref "C81") (pin "2") (pinfunction "2_2") (pintype "passive"))
      (node (ref "L1") (pin "2") (pinfunction "2_2") (pintype "passive"))
      (node (ref "R54") (pin "1") (pinfunction "1_1") (pintype "passive"))
      (node (ref "R73") (pin "2") (pinfunction "2_2") (pintype "passive"))
      (node (ref "U12") (pin "2") (pinfunction "VIN_2") (pintype "power_in"))
      (node (ref "U6") (pin "2") (pinfunction "VIN_2") (pintype "power_in"))
      (node (ref "U8") (pin "2") (pinfunction "VIN_2") (pintype "power_in"))
      (node (ref "U9") (pin "2") (pinfunction "VIN_2") (pintype "power_in"))
    )
    (net (code "12") (name "DDR3_VREF") (class "Default")
      (node (ref "C92") (pin "2") (pinfunction "2_2") (pintype "passive"))
      (node (ref "C93") (pin "2") (pinfunction "2_2") (pintype "passive"))
      (node (ref "U7") (pin "8") (pinfunction "VTTREF_8") (pintype "output"))
    )
    (net (code "13") (name "GND") (class "Default")
      (node (ref "C100") (pin "1") (pinfunction "1_1") (pintype "passive"))
      (node (ref "C101") (pin "1") (pinfunction "1_1") (pintype "passive"))
      (node (ref "C103") (pin "2") (pinfunction "2_2") (pintype "passive"))
      (node (ref "C104") (pin "2") (pinfunction "2_2") (pintype "passive"))
      (node (ref "C106") (pin "1") (pinfunction "1_1") (pintype "passive"))
      (node (ref "C107") (pin "1") (pinfunction "1_1") (pintype "passive"))
      (node (ref "C108") (pin "2") (pinfunction "2_2") (pintype "passive"))
      (node (ref "C109") (pin "2") (pinfunction "2_2") (pintype "passive"))
      (node (ref "C110") (pin "1") (pinfunction "1_1") (pintype "passive"))
      (node (ref "C115") (pin "1") (pinfunction "1_1") (pintype "passive"))
      (node (ref "C116") (pin "1") (pinfunction "1_1") (pintype "passive"))
      (node (ref "C118") (pin "2") (pinfunction "2_2") (pintype "passive"))
      (node (ref "C119") (pin "2") (pinfunction "2_2") (pintype "passive"))
      (node (ref "C121") (pin "1") (pinfunction "1_1") (pintype "passive"))
      (node (ref "C122") (pin "1") (pinfunction "1_1") (pintype "passive"))
      (node (ref "C123") (pin "2") (pinfunction "2_2") (pintype "passive"))
      (node (ref "C124") (pin "2") (pinfunction "2_2") (pintype "passive"))
      (node (ref "C138") (pin "1") (pinfunction "1_1") (pintype "passive"))
      (node (ref "C139") (pin "1") (pinfunction "1_1") (pintype "passive"))
      (node (ref "C141") (pin "2") (pinfunction "2_2") (pintype "passive"))
      (node (ref "C142") (pin "2") (pinfunction "2_2") (pintype "passive"))
      (node (ref "C144") (pin "1") (pinfunction "1_1") (pintype "passive"))
      (node (ref "C145") (pin "1") (pinfunction "1_1") (pintype "passive"))
      (node (ref "C146") (pin "2") (pinfunction "2_2") (pintype "passive"))
      (node (ref "C147") (pin "2") (pinfunction "2_2") (pintype "passive"))
      (node (ref "C70") (pin "1") (pinfunction "1_1") (pintype "passive"))
      (node (ref "C71") (pin "1") (pinfunction "1_1") (pintype "passive"))
      (node (ref "C73") (pin "2") (pinfunction "2_2") (pintype "passive"))
      (node (ref "C74") (pin "2") (pinfunction "2_2") (pintype "passive"))
      (node (ref "C76") (pin "1") (pinfunction "1_1") (pintype "passive"))
      (node (ref "C77") (pin "1") (pinfunction "1_1") (pintype "passive"))
      (node (ref "C79") (pin "2") (pinfunction "2_2") (pintype "passive"))
      (node (ref "C80") (pin "1") (pinfunction "1_1") (pintype "passive"))
      (node (ref "C81") (pin "1") (pinfunction "1_1") (pintype "passive"))
      (node (ref "C83") (pin "2") (pinfunction "2_2") (pintype "passive"))
      (node (ref "C84") (pin "2") (pinfunction "2_2") (pintype "passive"))
      (node (ref "C86") (pin "1") (pinfunction "1_1") (pintype "passive"))
      (node (ref "C87") (pin "1") (pinfunction "1_1") (pintype "passive"))
      (node (ref "C88") (pin "2") (pinfunction "2_2") (pintype "passive"))
      (node (ref "C89") (pin "1") (pinfunction "1_1") (pintype "passive"))
      (node (ref "C90") (pin "1") (pinfunction "1_1") (pintype "passive"))
      (node (ref "C91") (pin "2") (pinfunction "2_2") (pintype "passive"))
      (node (ref "C92") (pin "1") (pinfunction "1_1") (pintype "passive"))
      (node (ref "C93") (pin "1") (pinfunction "1_1") (pintype "passive"))
      (node (ref "C94") (pin "1") (pinfunction "1_1") (pintype "passive"))
      (node (ref "C95") (pin "1") (pinfunction "1_1") (pintype "passive"))
      (node (ref "C96") (pin "1") (pinfunction "1_1") (pintype "passive"))
      (node (ref "C97") (pin "1") (pinfunction "1_1") (pintype "passive"))
      (node (ref "C98") (pin "1") (pinfunction "1_1") (pintype "passive"))
      (node (ref "C99") (pin "1") (pinfunction "1_1") (pintype "passive"))
      (node (ref "FB4") (pin "1") (pinfunction "1_1") (pintype "passive"))
      (node (ref "R100") (pin "2") (pinfunction "2_2") (pintype "passive"))
      (node (ref "R57") (pin "2") (pinfunction "2_2") (pintype "passive"))
      (node (ref "R63") (pin "2") (pinfunction "2_2") (pintype "passive"))
      (node (ref "R69") (pin "2") (pinfunction "2_2") (pintype "passive"))
      (node (ref "R75") (pin "2") (pinfunction "2_2") (pintype "passive"))
      (node (ref "U12") (pin "4") (pinfunction "GND_4") (pintype "power_in"))
      (node (ref "U5") (pin "4") (pinfunction "GND_4") (pintype "power_in"))
      (node (ref "U6") (pin "4") (pinfunction "GND_4") (pintype "power_in"))
      (node (ref "U7") (pin "3") (pinfunction "GND_3") (pintype "power_in"))
      (node (ref "U7") (pin "EPAD") (pinfunction "EPAD_EPAD") (pintype "power_in"))
      (node (ref "U8") (pin "4") (pinfunction "GND_4") (pintype "power_in"))
      (node (ref "U9") (pin "4") (pinfunction "GND_4") (pintype "power_in"))
    )
    (net (code "14") (name "Net-(C72-Pad2)") (class "Default")
      (node (ref "C72") (pin "2") (pinfunction "2_2") (pintype "passive"))
      (node (ref "R52") (pin "1") (pinfunction "1_1") (pintype "passive"))
    )
    (net (code "15") (name "Net-(C75-Pad1)") (class "Default")
      (node (ref "C75") (pin "1") (pinfunction "1_1") (pintype "passive"))
      (node (ref "R54") (pin "2") (pinfunction "2_2") (pintype "passive"))
      (node (ref "R56") (pin "2") (pinfunction "2_2") (pintype "passive"))
      (node (ref "R57") (pin "1") (pinfunction "1_1") (pintype "passive"))
    )
    (net (code "16") (name "Net-(C82-Pad2)") (class "Default")
      (node (ref "C82") (pin "2") (pinfunction "2_2") (pintype "passive"))
      (node (ref "R58") (pin "1") (pinfunction "1_1") (pintype "passive"))
    )
    (net (code "17") (name "Net-(C85-Pad1)") (class "Default")
      (node (ref "C85") (pin "1") (pinfunction "1_1") (pintype "passive"))
      (node (ref "R60") (pin "2") (pinfunction "2_2") (pintype "passive"))
      (node (ref "R62") (pin "2") (pinfunction "2_2") (pintype "passive"))
      (node (ref "R63") (pin "1") (pinfunction "1_1") (pintype "passive"))
    )
    (net (code "18") (name "Net-(C102-Pad2)") (class "Default")
      (node (ref "C102") (pin "2") (pinfunction "2_2") (pintype "passive"))
      (node (ref "R64") (pin "1") (pinfunction "1_1") (pintype "passive"))
    )
    (net (code "19") (name "Net-(C105-Pad1)") (class "Default")
      (node (ref "C105") (pin "1") (pinfunction "1_1") (pintype "passive"))
      (node (ref "R66") (pin "2") (pinfunction "2_2") (pintype "passive"))
      (node (ref "R68") (pin "2") (pinfunction "2_2") (pintype "passive"))
      (node (ref "R69") (pin "1") (pinfunction "1_1") (pintype "passive"))
    )
    (net (code "20") (name "Net-(C117-Pad2)") (class "Default")
      (node (ref "C117") (pin "2") (pinfunction "2_2") (pintype "passive"))
      (node (ref "R70") (pin "1") (pinfunction "1_1") (pintype "passive"))
    )
    (net (code "21") (name "Net-(C120-Pad1)") (class "Default")
      (node (ref "C120") (pin "1") (pinfunction "1_1") (pintype "passive"))
      (node (ref "R72") (pin "2") (pinfunction "2_2") (pintype "passive"))
      (node (ref "R74") (pin "2") (pinfunction "2_2") (pintype "passive"))
      (node (ref "R75") (pin "1") (pinfunction "1_1") (pintype "passive"))
    )
    (net (code "22") (name "Net-(C140-Pad2)") (class "Default")
      (node (ref "C140") (pin "2") (pinfunction "2_2") (pintype "passive"))
      (node (ref "R96") (pin "1") (pinfunction "1_1") (pintype "passive"))
    )
    (net (code "23") (name "Net-(C143-Pad1)") (class "Default")
      (node (ref "C143") (pin "1") (pinfunction "1_1") (pintype "passive"))
      (node (ref "R100") (pin "1") (pinfunction "1_1") (pintype "passive"))
      (node (ref "R97") (pin "2") (pinfunction "2_2") (pintype "passive"))
      (node (ref "R99") (pin "2") (pinfunction "2_2") (pintype "passive"))
    )
    (net (code "24") (name "Net-(U5-BST)") (class "Default")
      (node (ref "R52") (pin "2") (pinfunction "2_2") (pintype "passive"))
      (node (ref "U5") (pin "5") (pinfunction "BST_5") (pintype "passive"))
    )
    (net (code "25") (name "Net-(U5-EN)") (class "Default")
      (node (ref "R53") (pin "1") (pinfunction "1_1") (pintype "passive"))
      (node (ref "U5") (pin "6") (pinfunction "EN_6") (pintype "passive"))
    )
    (net (code "26") (name "Net-(U5-FB)") (class "Default")
      (node (ref "R56") (pin "1") (pinfunction "1_1") (pintype "passive"))
      (node (ref "U5") (pin "8") (pinfunction "FB_8") (pintype "passive"))
    )
    (net (code "27") (name "Net-(U5-SS)") (class "Default")
      (node (ref "C79") (pin "1") (pinfunction "1_1") (pintype "passive"))
      (node (ref "U5") (pin "7") (pinfunction "SS_7") (pintype "passive"))
    )
    (net (code "28") (name "Net-(U5-SW)") (class "Default")
      (node (ref "C72") (pin "1") (pinfunction "1_1") (pintype "passive"))
      (node (ref "L1") (pin "1") (pinfunction "1_1") (pintype "passive"))
      (node (ref "U5") (pin "3") (pinfunction "SW_3") (pintype "output"))
    )
    (net (code "29") (name "Net-(U6-BST)") (class "Default")
      (node (ref "R58") (pin "2") (pinfunction "2_2") (pintype "passive"))
      (node (ref "U6") (pin "5") (pinfunction "BST_5") (pintype "passive"))
    )
    (net (code "30") (name "Net-(U6-FB)") (class "Default")
      (node (ref "R62") (pin "1") (pinfunction "1_1") (pintype "passive"))
      (node (ref "U6") (pin "8") (pinfunction "FB_8") (pintype "passive"))
    )
    (net (code "31") (name "Net-(U6-SS)") (class "Default")
      (node (ref "C91") (pin "1") (pinfunction "1_1") (pintype "passive"))
      (node (ref "U6") (pin "7") (pinfunction "SS_7") (pintype "passive"))
    )
    (net (code "32") (name "Net-(U6-SW)") (class "Default")
      (node (ref "C82") (pin "1") (pinfunction "1_1") (pintype "passive"))
      (node (ref "L2") (pin "1") (pinfunction "1_1") (pintype "passive"))
      (node (ref "U6") (pin "3") (pinfunction "SW_3") (pintype "output"))
    )
    (net (code "33") (name "Net-(U8-BST)") (class "Default")
      (node (ref "R64") (pin "2") (pinfunction "2_2") (pintype "passive"))
      (node (ref "U8") (pin "5") (pinfunction "BST_5") (pintype "passive"))
    )
    (net (code "34") (name "Net-(U8-FB)") (class "Default")
      (node (ref "R68") (pin "1") (pinfunction "1_1") (pintype "passive"))
      (node (ref "U8") (pin "8") (pinfunction "FB_8") (pintype "passive"))
    )
    (net (code "35") (name "Net-(U8-SS)") (class "Default")
      (node (ref "C109") (pin "1") (pinfunction "1_1") (pintype "passive"))
      (node (ref "U8") (pin "7") (pinfunction "SS_7") (pintype "passive"))
    )
    (net (code "36") (name "Net-(U8-SW)") (class "Default")
      (node (ref "C102") (pin "1") (pinfunction "1_1") (pintype "passive"))
      (node (ref "L3") (pin "1") (pinfunction "1_1") (pintype "passive"))
      (node (ref "U8") (pin "3") (pinfunction "SW_3") (pintype "output"))
    )
    (net (code "37") (name "Net-(U9-BST)") (class "Default")
      (node (ref "R70") (pin "2") (pinfunction "2_2") (pintype "passive"))
      (node (ref "U9") (pin "5") (pinfunction "BST_5") (pintype "passive"))
    )
    (net (code "38") (name "Net-(U9-EN)") (class "Default")
      (node (ref "R73") (pin "1") (pinfunction "1_1") (pintype "passive"))
      (node (ref "U9") (pin "6") (pinfunction "EN_6") (pintype "passive"))
    )
    (net (code "39") (name "Net-(U9-FB)") (class "Default")
      (node (ref "R74") (pin "1") (pinfunction "1_1") (pintype "passive"))
      (node (ref "U9") (pin "8") (pinfunction "FB_8") (pintype "passive"))
    )
    (net (code "40") (name "Net-(U9-SS)") (class "Default")
      (node (ref "C124") (pin "1") (pinfunction "1_1") (pintype "passive"))
      (node (ref "U9") (pin "7") (pinfunction "SS_7") (pintype "passive"))
    )
    (net (code "41") (name "Net-(U9-SW)") (class "Default")
      (node (ref "C117") (pin "1") (pinfunction "1_1") (pintype "passive"))
      (node (ref "L4") (pin "1") (pinfunction "1_1") (pintype "passive"))
      (node (ref "U9") (pin "3") (pinfunction "SW_3") (pintype "output"))
    )
    (net (code "42") (name "Net-(U12-BST)") (class "Default")
      (node (ref "R96") (pin "2") (pinfunction "2_2") (pintype "passive"))
      (node (ref "U12") (pin "5") (pinfunction "BST_5") (pintype "passive"))
    )
    (net (code "43") (name "Net-(U12-FB)") (class "Default")
      (node (ref "R99") (pin "1") (pinfunction "1_1") (pintype "passive"))
      (node (ref "U12") (pin "8") (pinfunction "FB_8") (pintype "passive"))
    )
    (net (code "44") (name "Net-(U12-SS)") (class "Default")
      (node (ref "C147") (pin "1") (pinfunction "1_1") (pintype "passive"))
      (node (ref "U12") (pin "7") (pinfunction "SS_7") (pintype "passive"))
    )
    (net (code "45") (name "Net-(U12-SW)") (class "Default")
      (node (ref "C140") (pin "1") (pinfunction "1_1") (pintype "passive"))
      (node (ref "L5") (pin "1") (pinfunction "1_1") (pintype "passive"))
      (node (ref "U12") (pin "3") (pinfunction "SW_3") (pintype "output"))
    )
    (net (code "46") (name "XADC1V8") (class "Default")
      (node (ref "C111") (pin "2") (pinfunction "2_2") (pintype "passive"))
      (node (ref "C112") (pin "2") (pinfunction "2_2") (pintype "passive"))
      (node (ref "FB3") (pin "2") (pinfunction "2_2") (pintype "passive"))
      (node (ref "U10") (pin "1") (pinfunction "IN_1") (pintype "power_in"))
    )
    (net (code "47") (name "XADCGND") (class "Default")
      (node (ref "C111") (pin "1") (pinfunction "1_1") (pintype "passive"))
      (node (ref "C112") (pin "1") (pinfunction "1_1") (pintype "passive"))
      (node (ref "C113") (pin "1") (pinfunction "1_1") (pintype "passive"))
      (node (ref "C114") (pin "1") (pinfunction "1_1") (pintype "passive"))
      (node (ref "FB4") (pin "2") (pinfunction "2_2") (pintype "passive"))
      (node (ref "U10") (pin "3") (pinfunction "GND_3") (pintype "power_in"))
    )
    (net (code "48") (name "XADCVREF") (class "Default")
      (node (ref "C113") (pin "2") (pinfunction "2_2") (pintype "passive"))
      (node (ref "C114") (pin "2") (pinfunction "2_2") (pintype "passive"))
      (node (ref "U10") (pin "2") (pinfunction "OUT_2") (pintype "power_in"))
    )
    (net (code "49") (name "unconnected-(U5-PG-Pad1)") (class "Default")
      (node (ref "U5") (pin "1") (pinfunction "PG_1") (pintype "output+no_connect"))
    )
  )
)
